# Conductance.net
KiCad netlist of a schematic drawn in EAGLE
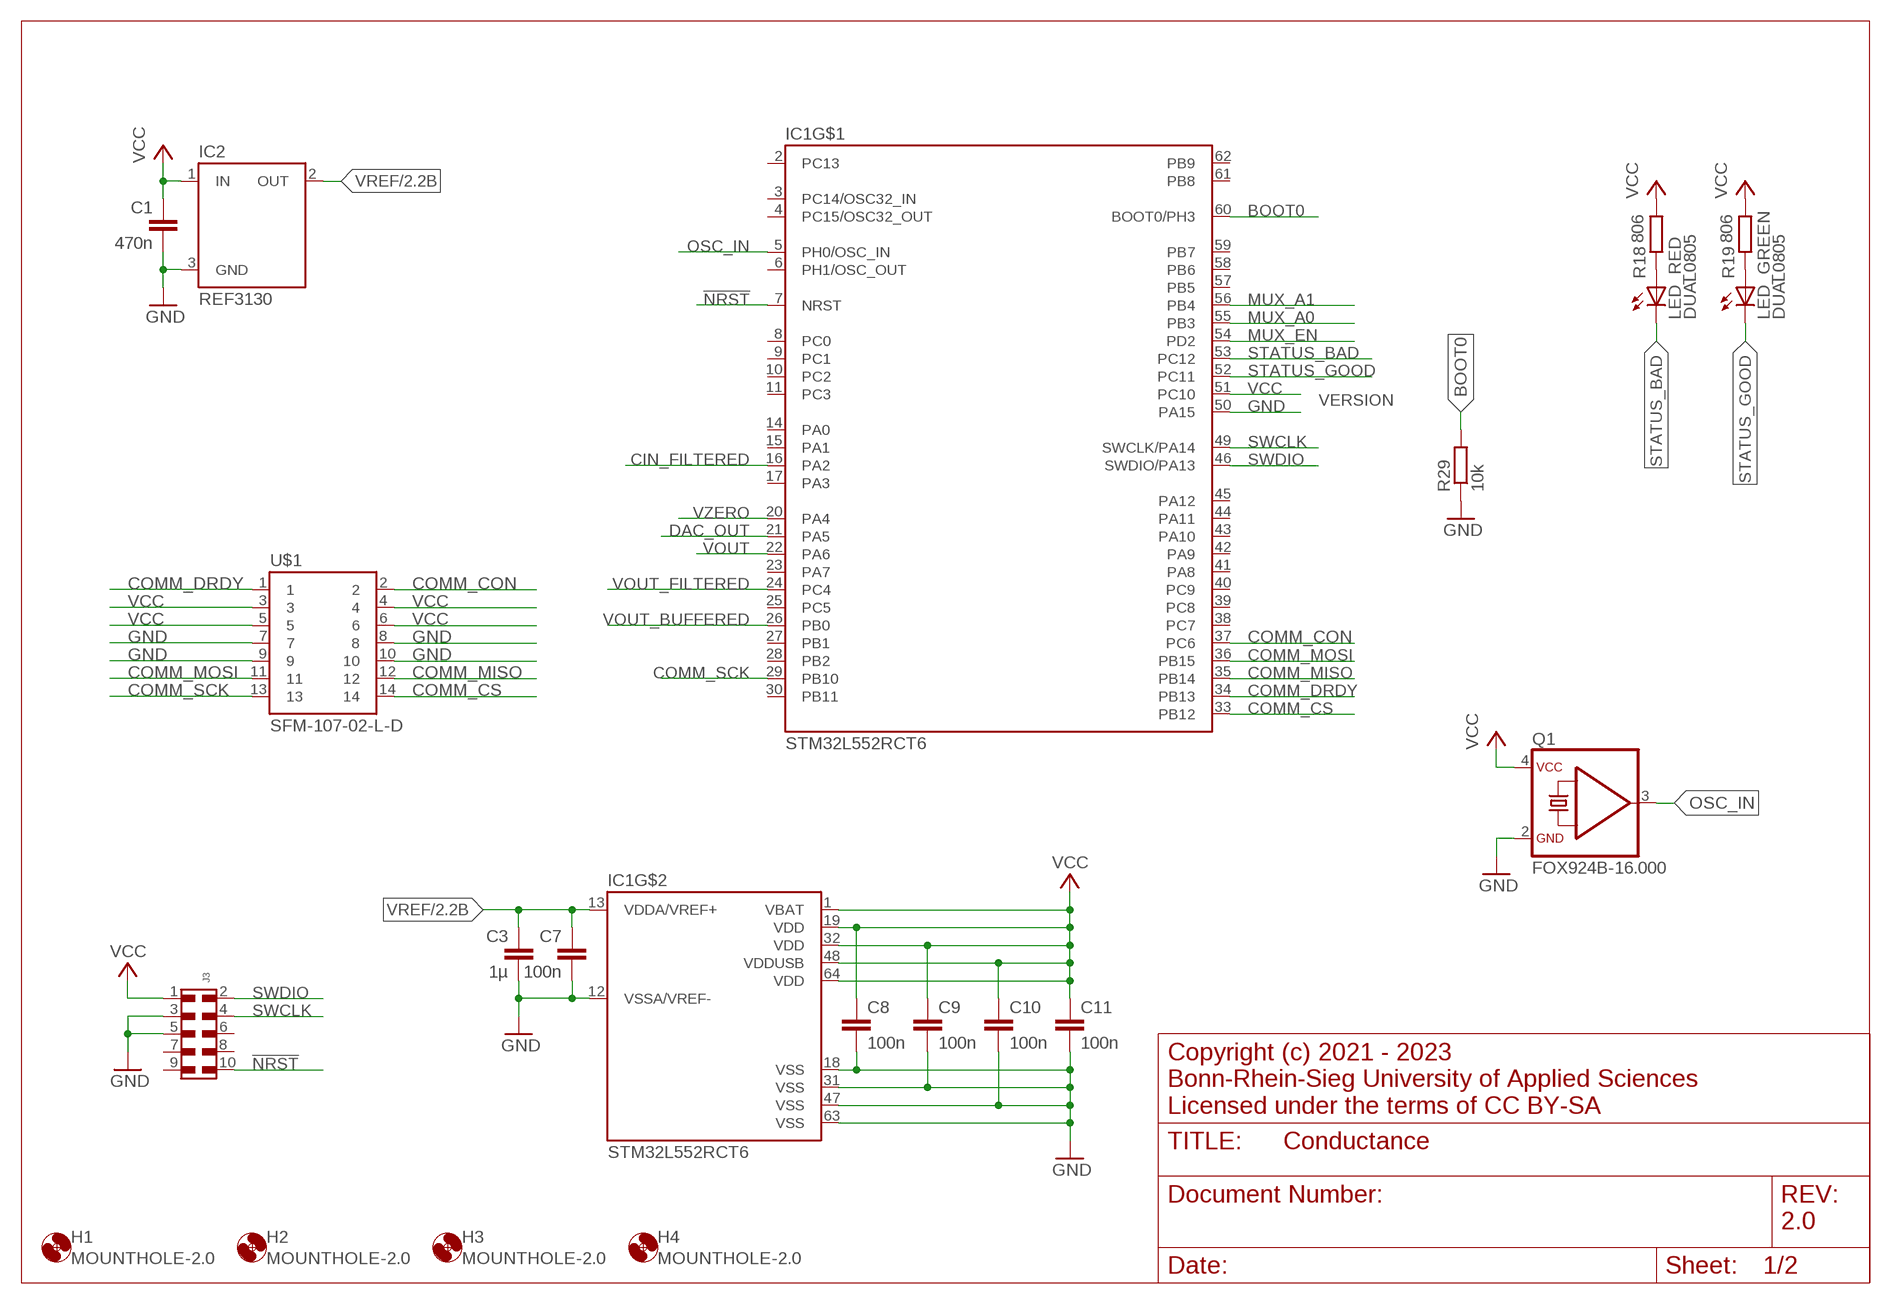
[diagram p0: schematic, sheet 1]
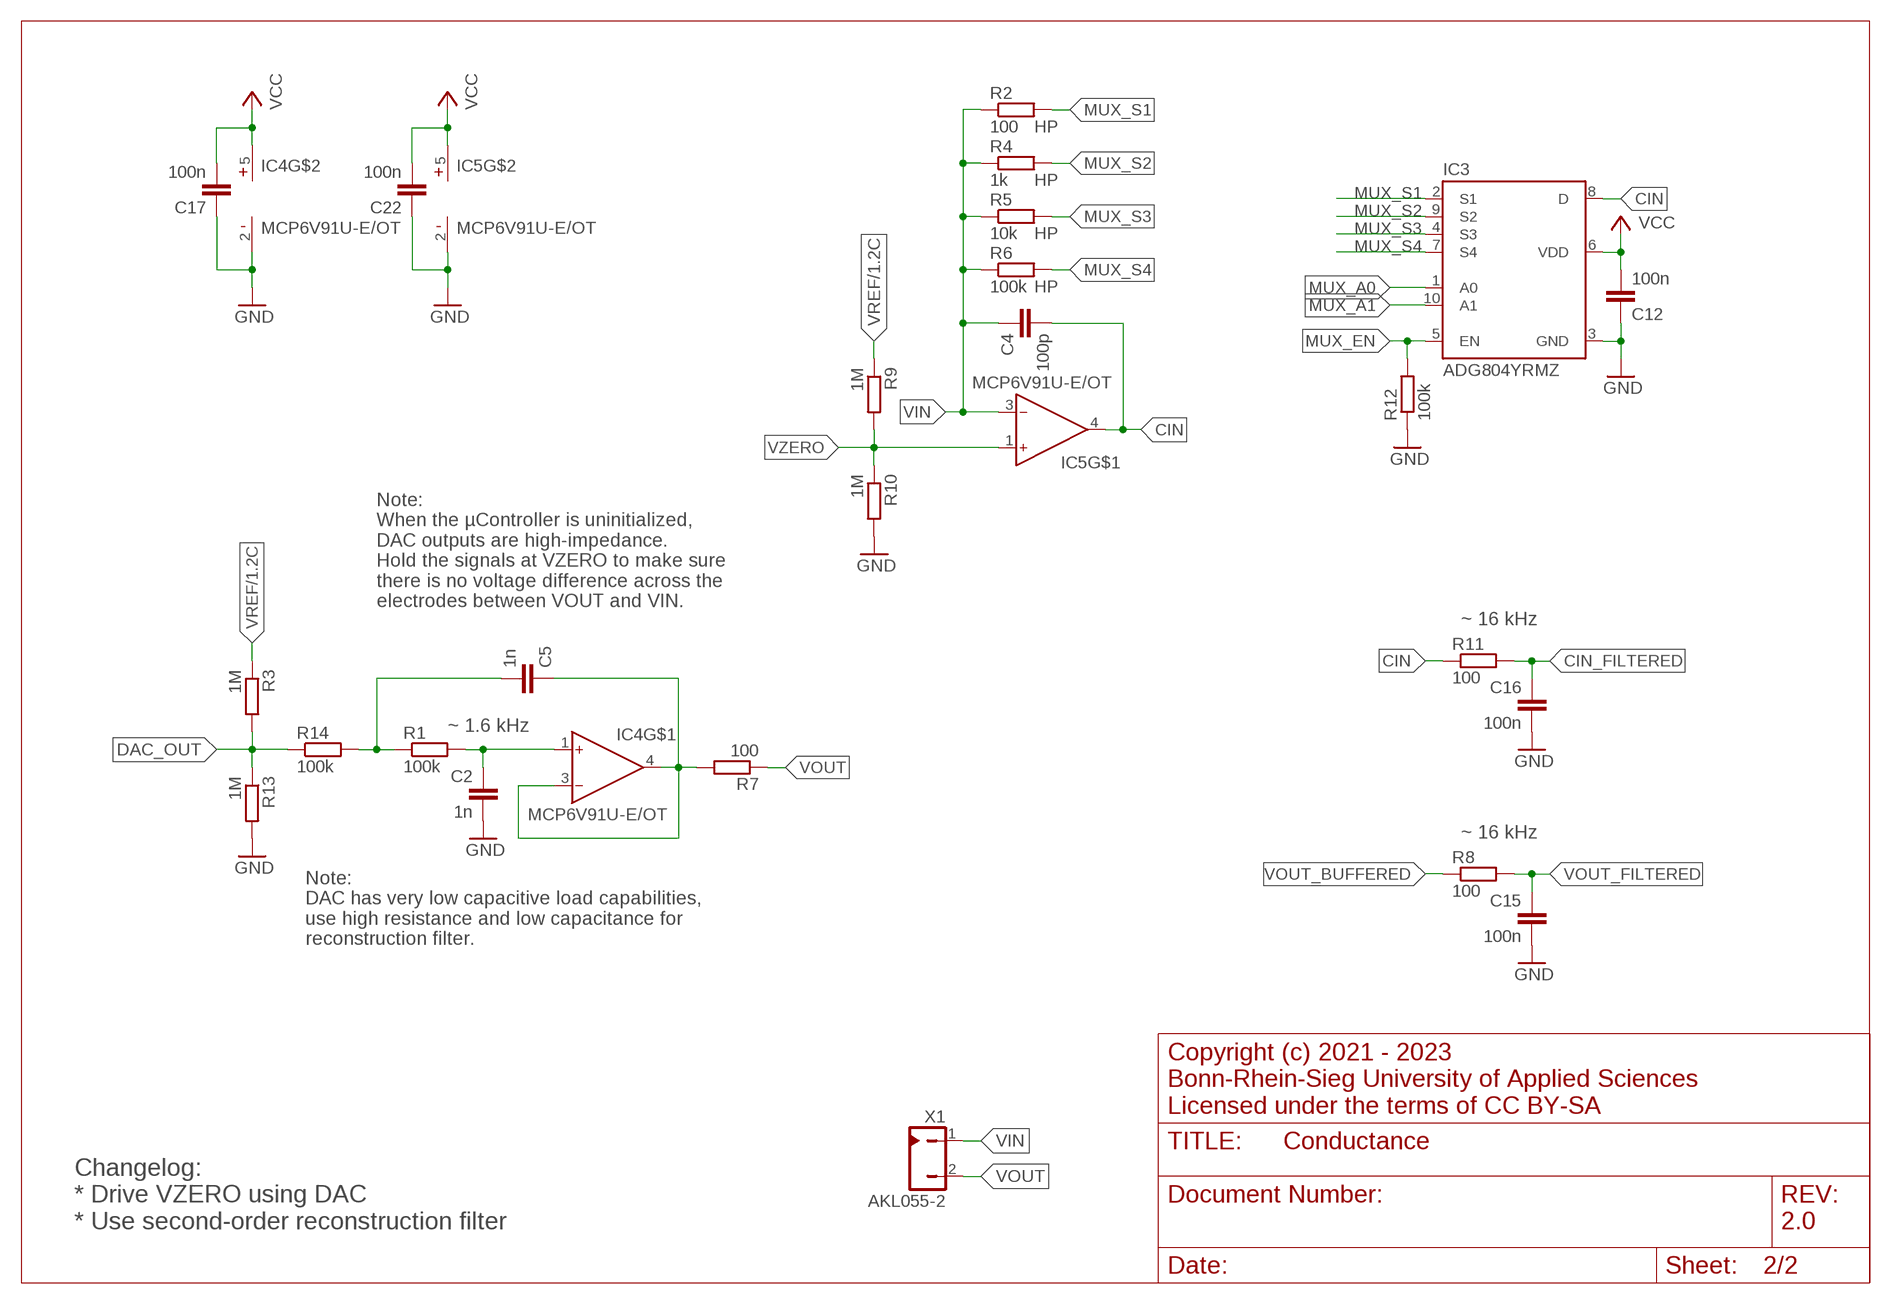
[diagram p1: schematic, sheet 2]

(export (version "E")
  (design (tool "Eeschema 10.0.6"))
  (components
    (comp (ref "C1")
      (value "470n")
      (footprint "eagle-import:C0603")
      (libsource (lib "eagle-import") (part "C-EUC0603"))
    )
    (comp (ref "C3")
      (value "1µ")
      (footprint "eagle-import:C0603")
      (libsource (lib "eagle-import") (part "C-EUC0603"))
    )
    (comp (ref "C7")
      (value "100n")
      (footprint "eagle-import:C0603")
      (libsource (lib "eagle-import") (part "C-EUC0603"))
    )
    (comp (ref "C8")
      (value "100n")
      (footprint "eagle-import:C0603")
      (libsource (lib "eagle-import") (part "C-EUC0603"))
    )
    (comp (ref "C9")
      (value "100n")
      (footprint "eagle-import:C0603")
      (libsource (lib "eagle-import") (part "C-EUC0603"))
    )
    (comp (ref "C10")
      (value "100n")
      (footprint "eagle-import:C0603")
      (libsource (lib "eagle-import") (part "C-EUC0603"))
    )
    (comp (ref "C11")
      (value "100n")
      (footprint "eagle-import:C0603")
      (libsource (lib "eagle-import") (part "C-EUC0603"))
    )
    (comp (ref "H1")
      (value "MOUNTHOLE-2.0")
      (footprint "eagle-import:2.0")
      (libsource (lib "eagle-import") (part "MOUNTHOLE-2.0"))
    )
    (comp (ref "H2")
      (value "MOUNTHOLE-2.0")
      (footprint "eagle-import:2.0")
      (libsource (lib "eagle-import") (part "MOUNTHOLE-2.0"))
    )
    (comp (ref "H3")
      (value "MOUNTHOLE-2.0")
      (footprint "eagle-import:2.0")
      (libsource (lib "eagle-import") (part "MOUNTHOLE-2.0"))
    )
    (comp (ref "H4")
      (value "MOUNTHOLE-2.0")
      (footprint "eagle-import:2.0")
      (libsource (lib "eagle-import") (part "MOUNTHOLE-2.0"))
    )
    (comp (ref "IC1")
      (value "STM32L552RCT6")
      (footprint "eagle-import:LQFP64")
      (libsource (lib "eagle-import") (part "STM32L552R?T6C"))
    )
    (comp (ref "IC2")
      (value "REF3130")
      (footprint "eagle-import:SOT23")
      (libsource (lib "eagle-import") (part "REF3130"))
    )
    (comp (ref "J3")
      (value "6210XX21021_62101021021")
      (footprint "eagle-import:62101021021")
      (libsource (lib "eagle-import") (part "6210XX21021_62101021021"))
    )
    (comp (ref "LED_")
      (value "DUAL0805")
      (footprint "eagle-import:CHIPLEDX2")
      (libsource (lib "eagle-import") (part "DUAL0805"))
    )
    (comp (ref "Q1")
      (value "FOX924B-16.000")
      (footprint "eagle-import:FOX924B")
      (libsource (lib "eagle-import") (part "FOX924B-16.000"))
    )
    (comp (ref "R18")
      (value "806")
      (footprint "eagle-import:R0603")
      (libsource (lib "eagle-import") (part "R-EU_R0603"))
    )
    (comp (ref "R19")
      (value "806")
      (footprint "eagle-import:R0603")
      (libsource (lib "eagle-import") (part "R-EU_R0603"))
    )
    (comp (ref "R29")
      (value "10k")
      (footprint "eagle-import:R0603")
      (libsource (lib "eagle-import") (part "R-EU_R0603"))
    )
    (comp (ref "U$1")
      (value "SFM-107-02-L-D")
      (footprint "eagle-import:SAMTEC-SFM-107-02-L-D")
      (libsource (lib "eagle-import") (part "SFM-107-02-L-D"))
    )
    (comp (ref "C2")
      (value "1n")
      (footprint "eagle-import:C0603")
      (libsource (lib "eagle-import") (part "C-EUC0603"))
    )
    (comp (ref "C4")
      (value "100p")
      (footprint "eagle-import:C0603")
      (libsource (lib "eagle-import") (part "C-EUC0603"))
    )
    (comp (ref "C5")
      (value "1n")
      (footprint "eagle-import:C0603")
      (libsource (lib "eagle-import") (part "C-EUC0603"))
    )
    (comp (ref "C12")
      (value "100n")
      (footprint "eagle-import:C0603")
      (libsource (lib "eagle-import") (part "C-EUC0603"))
    )
    (comp (ref "C15")
      (value "100n")
      (footprint "eagle-import:C0603")
      (libsource (lib "eagle-import") (part "C-EUC0603"))
    )
    (comp (ref "C16")
      (value "100n")
      (footprint "eagle-import:C0603")
      (libsource (lib "eagle-import") (part "C-EUC0603"))
    )
    (comp (ref "C17")
      (value "100n")
      (footprint "eagle-import:C0603")
      (libsource (lib "eagle-import") (part "C-EUC0603"))
    )
    (comp (ref "C22")
      (value "100n")
      (footprint "eagle-import:C0603")
      (libsource (lib "eagle-import") (part "C-EUC0603"))
    )
    (comp (ref "IC3")
      (value "ADG804YRMZ")
      (footprint "eagle-import:MSOP10")
      (libsource (lib "eagle-import") (part "ADG804YRMZ"))
    )
    (comp (ref "IC4")
      (value "MCP6V91U-E/OT")
      (footprint "eagle-import:SOT23-5")
      (libsource (lib "eagle-import") (part "MCP6V91U-/?OTE"))
    )
    (comp (ref "IC5")
      (value "MCP6V91U-E/OT")
      (footprint "eagle-import:SOT23-5")
      (libsource (lib "eagle-import") (part "MCP6V91U-/?OTE"))
    )
    (comp (ref "R1")
      (value "100k")
      (footprint "eagle-import:R0603")
      (libsource (lib "eagle-import") (part "R-EU_R0603"))
    )
    (comp (ref "R2")
      (value "100")
      (footprint "eagle-import:R0603")
      (libsource (lib "eagle-import") (part "R-EU_R0603"))
    )
    (comp (ref "R3")
      (value "1M")
      (footprint "eagle-import:R0603")
      (libsource (lib "eagle-import") (part "R-EU_R0603"))
    )
    (comp (ref "R4")
      (value "1k")
      (footprint "eagle-import:R0603")
      (libsource (lib "eagle-import") (part "R-EU_R0603"))
    )
    (comp (ref "R5")
      (value "10k")
      (footprint "eagle-import:R0603")
      (libsource (lib "eagle-import") (part "R-EU_R0603"))
    )
    (comp (ref "R6")
      (value "100k")
      (footprint "eagle-import:R0603")
      (libsource (lib "eagle-import") (part "R-EU_R0603"))
    )
    (comp (ref "R7")
      (value "100")
      (footprint "eagle-import:R0603")
      (libsource (lib "eagle-import") (part "R-EU_R0603"))
    )
    (comp (ref "R8")
      (value "100")
      (footprint "eagle-import:R0603")
      (libsource (lib "eagle-import") (part "R-EU_R0603"))
    )
    (comp (ref "R9")
      (value "1M")
      (footprint "eagle-import:R0603")
      (libsource (lib "eagle-import") (part "R-EU_R0603"))
    )
    (comp (ref "R10")
      (value "1M")
      (footprint "eagle-import:R0603")
      (libsource (lib "eagle-import") (part "R-EU_R0603"))
    )
    (comp (ref "R11")
      (value "100")
      (footprint "eagle-import:R0603")
      (libsource (lib "eagle-import") (part "R-EU_R0603"))
    )
    (comp (ref "R12")
      (value "100k")
      (footprint "eagle-import:R0603")
      (libsource (lib "eagle-import") (part "R-EU_R0603"))
    )
    (comp (ref "R13")
      (value "1M")
      (footprint "eagle-import:R0603")
      (libsource (lib "eagle-import") (part "R-EU_R0603"))
    )
    (comp (ref "R14")
      (value "100k")
      (footprint "eagle-import:R0603")
      (libsource (lib "eagle-import") (part "R-EU_R0603"))
    )
    (comp (ref "X1")
      (value "AKL055-2")
      (footprint "eagle-import:AKL055-2")
      (libsource (lib "eagle-import") (part "AKL055-2"))
    )
  )
  (nets
    (net (code "1") (name "BOOT0") (class "Default")
      (node (ref "IC1") (pin "60") (pinfunction "BOOT0/PH3_60") (pintype "bidirectional"))
      (node (ref "R29") (pin "2") (pinfunction "2_2") (pintype "passive"))
    )
    (net (code "2") (name "CIN") (class "Default")
      (node (ref "C4") (pin "2") (pinfunction "2_2") (pintype "passive"))
      (node (ref "IC3") (pin "8") (pinfunction "D_8") (pintype "bidirectional"))
      (node (ref "IC5") (pin "4") (pinfunction "OUT_4") (pintype "output"))
      (node (ref "R11") (pin "1") (pinfunction "1_1") (pintype "passive"))
    )
    (net (code "3") (name "CIN_FILTERED") (class "Default")
      (node (ref "C16") (pin "1") (pinfunction "1_1") (pintype "passive"))
      (node (ref "IC1") (pin "16") (pinfunction "PA2_16") (pintype "bidirectional"))
      (node (ref "R11") (pin "2") (pinfunction "2_2") (pintype "passive"))
    )
    (net (code "4") (name "COMM_CON") (class "Default")
      (node (ref "IC1") (pin "37") (pinfunction "PC6_37") (pintype "bidirectional"))
      (node (ref "U$1") (pin "2") (pinfunction "2_2") (pintype "passive"))
    )
    (net (code "5") (name "COMM_CS") (class "Default")
      (node (ref "IC1") (pin "33") (pinfunction "PB12_33") (pintype "bidirectional"))
      (node (ref "U$1") (pin "14") (pinfunction "14_14") (pintype "passive"))
    )
    (net (code "6") (name "COMM_DRDY") (class "Default")
      (node (ref "IC1") (pin "34") (pinfunction "PB13_34") (pintype "bidirectional"))
      (node (ref "U$1") (pin "1") (pinfunction "1_1") (pintype "passive"))
    )
    (net (code "7") (name "COMM_MISO") (class "Default")
      (node (ref "IC1") (pin "35") (pinfunction "PB14_35") (pintype "bidirectional"))
      (node (ref "U$1") (pin "12") (pinfunction "12_12") (pintype "passive"))
    )
    (net (code "8") (name "COMM_MOSI") (class "Default")
      (node (ref "IC1") (pin "36") (pinfunction "PB15_36") (pintype "bidirectional"))
      (node (ref "U$1") (pin "11") (pinfunction "11_11") (pintype "passive"))
    )
    (net (code "9") (name "COMM_SCK") (class "Default")
      (node (ref "IC1") (pin "29") (pinfunction "PB10_29") (pintype "bidirectional"))
      (node (ref "U$1") (pin "13") (pinfunction "13_13") (pintype "passive"))
    )
    (net (code "10") (name "DAC_OUT") (class "Default")
      (node (ref "IC1") (pin "21") (pinfunction "PA5_21") (pintype "bidirectional"))
      (node (ref "R13") (pin "1") (pinfunction "1_1") (pintype "passive"))
      (node (ref "R14") (pin "1") (pinfunction "1_1") (pintype "passive"))
      (node (ref "R3") (pin "2") (pinfunction "2_2") (pintype "passive"))
    )
    (net (code "11") (name "GND") (class "Default")
      (node (ref "C1") (pin "2") (pinfunction "2_2") (pintype "passive"))
      (node (ref "C10") (pin "2") (pinfunction "2_2") (pintype "passive"))
      (node (ref "C11") (pin "2") (pinfunction "2_2") (pintype "passive"))
      (node (ref "C12") (pin "1") (pinfunction "1_1") (pintype "passive"))
      (node (ref "C15") (pin "2") (pinfunction "2_2") (pintype "passive"))
      (node (ref "C16") (pin "2") (pinfunction "2_2") (pintype "passive"))
      (node (ref "C17") (pin "1") (pinfunction "1_1") (pintype "passive"))
      (node (ref "C2") (pin "2") (pinfunction "2_2") (pintype "passive"))
      (node (ref "C22") (pin "1") (pinfunction "1_1") (pintype "passive"))
      (node (ref "C3") (pin "2") (pinfunction "2_2") (pintype "passive"))
      (node (ref "C7") (pin "2") (pinfunction "2_2") (pintype "passive"))
      (node (ref "C8") (pin "2") (pinfunction "2_2") (pintype "passive"))
      (node (ref "C9") (pin "2") (pinfunction "2_2") (pintype "passive"))
      (node (ref "IC1") (pin "12") (pinfunction "VSSA/VREF-_12") (pintype "bidirectional"))
      (node (ref "IC1") (pin "18") (pinfunction "VSS_18") (pintype "bidirectional"))
      (node (ref "IC1") (pin "31") (pinfunction "VSS_31") (pintype "bidirectional"))
      (node (ref "IC1") (pin "47") (pinfunction "VSS_47") (pintype "bidirectional"))
      (node (ref "IC1") (pin "50") (pinfunction "PA15_50") (pintype "bidirectional"))
      (node (ref "IC1") (pin "63") (pinfunction "VSS_63") (pintype "bidirectional"))
      (node (ref "IC2") (pin "3") (pinfunction "GND_3") (pintype "bidirectional"))
      (node (ref "IC3") (pin "3") (pinfunction "GND_3") (pintype "bidirectional"))
      (node (ref "IC4") (pin "2") (pinfunction "VSS_2") (pintype "power_in"))
      (node (ref "IC5") (pin "2") (pinfunction "VSS_2") (pintype "power_in"))
      (node (ref "J3") (pin "3") (pinfunction "3_3") (pintype "passive"))
      (node (ref "J3") (pin "5") (pinfunction "5_5") (pintype "passive"))
      (node (ref "Q1") (pin "2") (pinfunction "GND_2") (pintype "power_in"))
      (node (ref "R10") (pin "2") (pinfunction "2_2") (pintype "passive"))
      (node (ref "R12") (pin "1") (pinfunction "1_1") (pintype "passive"))
      (node (ref "R13") (pin "2") (pinfunction "2_2") (pintype "passive"))
      (node (ref "R29") (pin "1") (pinfunction "1_1") (pintype "passive"))
      (node (ref "U$1") (pin "10") (pinfunction "10_10") (pintype "passive"))
      (node (ref "U$1") (pin "7") (pinfunction "7_7") (pintype "passive"))
      (node (ref "U$1") (pin "8") (pinfunction "8_8") (pintype "passive"))
      (node (ref "U$1") (pin "9") (pinfunction "9_9") (pintype "passive"))
    )
    (net (code "12") (name "MUX_A0") (class "Default")
      (node (ref "IC1") (pin "55") (pinfunction "PB3_55") (pintype "bidirectional"))
      (node (ref "IC3") (pin "1") (pinfunction "A0_1") (pintype "bidirectional"))
    )
    (net (code "13") (name "MUX_A1") (class "Default")
      (node (ref "IC1") (pin "56") (pinfunction "PB4_56") (pintype "bidirectional"))
      (node (ref "IC3") (pin "10") (pinfunction "A1_10") (pintype "bidirectional"))
    )
    (net (code "14") (name "MUX_EN") (class "Default")
      (node (ref "IC1") (pin "54") (pinfunction "PD2_54") (pintype "bidirectional"))
      (node (ref "IC3") (pin "5") (pinfunction "EN_5") (pintype "bidirectional"))
      (node (ref "R12") (pin "2") (pinfunction "2_2") (pintype "passive"))
    )
    (net (code "15") (name "MUX_S1") (class "Default")
      (node (ref "IC3") (pin "2") (pinfunction "S1_2") (pintype "bidirectional"))
      (node (ref "R2") (pin "2") (pinfunction "2_2") (pintype "passive"))
    )
    (net (code "16") (name "MUX_S2") (class "Default")
      (node (ref "IC3") (pin "9") (pinfunction "S2_9") (pintype "bidirectional"))
      (node (ref "R4") (pin "2") (pinfunction "2_2") (pintype "passive"))
    )
    (net (code "17") (name "MUX_S3") (class "Default")
      (node (ref "IC3") (pin "4") (pinfunction "S3_4") (pintype "bidirectional"))
      (node (ref "R5") (pin "2") (pinfunction "2_2") (pintype "passive"))
    )
    (net (code "18") (name "MUX_S4") (class "Default")
      (node (ref "IC3") (pin "7") (pinfunction "S4_7") (pintype "bidirectional"))
      (node (ref "R6") (pin "2") (pinfunction "2_2") (pintype "passive"))
    )
    (net (code "19") (name "Net-(C5-Pad2)") (class "Default")
      (node (ref "C5") (pin "2") (pinfunction "2_2") (pintype "passive"))
      (node (ref "R1") (pin "1") (pinfunction "1_1") (pintype "passive"))
      (node (ref "R14") (pin "2") (pinfunction "2_2") (pintype "passive"))
    )
    (net (code "20") (name "Net-(IC4A-IN+)") (class "Default")
      (node (ref "C2") (pin "1") (pinfunction "1_1") (pintype "passive"))
      (node (ref "IC4") (pin "1") (pinfunction "IN+_1") (pintype "input"))
      (node (ref "R1") (pin "2") (pinfunction "2_2") (pintype "passive"))
    )
    (net (code "21") (name "Net-(IC4A-IN-)") (class "Default")
      (node (ref "C5") (pin "1") (pinfunction "1_1") (pintype "passive"))
      (node (ref "IC4") (pin "3") (pinfunction "IN-_3") (pintype "input"))
      (node (ref "IC4") (pin "4") (pinfunction "OUT_4") (pintype "output"))
      (node (ref "R7") (pin "2") (pinfunction "2_2") (pintype "passive"))
    )
    (net (code "22") (name "Net-(LED_A-A)") (class "Default")
      (node (ref "LED_") (pin "A2") (pinfunction "A_A2") (pintype "passive"))
      (node (ref "R19") (pin "1") (pinfunction "1_1") (pintype "passive"))
    )
    (net (code "23") (name "Net-(LED_B-A)") (class "Default")
      (node (ref "LED_") (pin "A1") (pinfunction "A_A1") (pintype "passive"))
      (node (ref "R18") (pin "1") (pinfunction "1_1") (pintype "passive"))
    )
    (net (code "24") (name "OSC_IN") (class "Default")
      (node (ref "IC1") (pin "5") (pinfunction "PH0/OSC_IN_5") (pintype "bidirectional"))
      (node (ref "Q1") (pin "3") (pinfunction "OUT_3") (pintype "output"))
    )
    (net (code "25") (name "STATUS_BAD") (class "Default")
      (node (ref "IC1") (pin "53") (pinfunction "PC12_53") (pintype "bidirectional"))
      (node (ref "LED_") (pin "C1") (pinfunction "C_C1") (pintype "passive"))
    )
    (net (code "26") (name "STATUS_GOOD") (class "Default")
      (node (ref "IC1") (pin "52") (pinfunction "PC11_52") (pintype "bidirectional"))
      (node (ref "LED_") (pin "C2") (pinfunction "C_C2") (pintype "passive"))
    )
    (net (code "27") (name "SWCLK") (class "Default")
      (node (ref "IC1") (pin "49") (pinfunction "SWCLK/PA14_49") (pintype "bidirectional"))
      (node (ref "J3") (pin "4") (pinfunction "4_4") (pintype "passive"))
    )
    (net (code "28") (name "SWDIO") (class "Default")
      (node (ref "IC1") (pin "46") (pinfunction "SWDIO/PA13_46") (pintype "bidirectional"))
      (node (ref "J3") (pin "2") (pinfunction "2_2") (pintype "passive"))
    )
    (net (code "29") (name "VCC") (class "Default")
      (node (ref "C1") (pin "1") (pinfunction "1_1") (pintype "passive"))
      (node (ref "C10") (pin "1") (pinfunction "1_1") (pintype "passive"))
      (node (ref "C11") (pin "1") (pinfunction "1_1") (pintype "passive"))
      (node (ref "C12") (pin "2") (pinfunction "2_2") (pintype "passive"))
      (node (ref "C17") (pin "2") (pinfunction "2_2") (pintype "passive"))
      (node (ref "C22") (pin "2") (pinfunction "2_2") (pintype "passive"))
      (node (ref "C8") (pin "1") (pinfunction "1_1") (pintype "passive"))
      (node (ref "C9") (pin "1") (pinfunction "1_1") (pintype "passive"))
      (node (ref "IC1") (pin "1") (pinfunction "VBAT_1") (pintype "bidirectional"))
      (node (ref "IC1") (pin "19") (pinfunction "VDD_19") (pintype "bidirectional"))
      (node (ref "IC1") (pin "32") (pinfunction "VDD_32") (pintype "bidirectional"))
      (node (ref "IC1") (pin "48") (pinfunction "VDDUSB_48") (pintype "bidirectional"))
      (node (ref "IC1") (pin "51") (pinfunction "PC10_51") (pintype "bidirectional"))
      (node (ref "IC1") (pin "64") (pinfunction "VDD_64") (pintype "bidirectional"))
      (node (ref "IC2") (pin "1") (pinfunction "IN_1") (pintype "bidirectional"))
      (node (ref "IC3") (pin "6") (pinfunction "VDD_6") (pintype "bidirectional"))
      (node (ref "IC4") (pin "5") (pinfunction "VDD_5") (pintype "power_in"))
      (node (ref "IC5") (pin "5") (pinfunction "VDD_5") (pintype "power_in"))
      (node (ref "J3") (pin "1") (pinfunction "1_1") (pintype "passive"))
      (node (ref "Q1") (pin "4") (pinfunction "VCC_4") (pintype "power_in"))
      (node (ref "R18") (pin "2") (pinfunction "2_2") (pintype "passive"))
      (node (ref "R19") (pin "2") (pinfunction "2_2") (pintype "passive"))
      (node (ref "U$1") (pin "3") (pinfunction "3_3") (pintype "passive"))
      (node (ref "U$1") (pin "4") (pinfunction "4_4") (pintype "passive"))
      (node (ref "U$1") (pin "5") (pinfunction "5_5") (pintype "passive"))
      (node (ref "U$1") (pin "6") (pinfunction "6_6") (pintype "passive"))
    )
    (net (code "30") (name "VIN") (class "Default")
      (node (ref "C4") (pin "1") (pinfunction "1_1") (pintype "passive"))
      (node (ref "IC5") (pin "3") (pinfunction "IN-_3") (pintype "input"))
      (node (ref "R2") (pin "1") (pinfunction "1_1") (pintype "passive"))
      (node (ref "R4") (pin "1") (pinfunction "1_1") (pintype "passive"))
      (node (ref "R5") (pin "1") (pinfunction "1_1") (pintype "passive"))
      (node (ref "R6") (pin "1") (pinfunction "1_1") (pintype "passive"))
      (node (ref "X1") (pin "1") (pinfunction "1_1") (pintype "passive"))
    )
    (net (code "31") (name "VOUT") (class "Default")
      (node (ref "IC1") (pin "22") (pinfunction "PA6_22") (pintype "bidirectional"))
      (node (ref "R7") (pin "1") (pinfunction "1_1") (pintype "passive"))
      (node (ref "X1") (pin "2") (pinfunction "4_2") (pintype "passive"))
    )
    (net (code "32") (name "VOUT_BUFFERED") (class "Default")
      (node (ref "IC1") (pin "26") (pinfunction "PB0_26") (pintype "bidirectional"))
      (node (ref "R8") (pin "1") (pinfunction "1_1") (pintype "passive"))
    )
    (net (code "33") (name "VOUT_FILTERED") (class "Default")
      (node (ref "C15") (pin "1") (pinfunction "1_1") (pintype "passive"))
      (node (ref "IC1") (pin "24") (pinfunction "PC4_24") (pintype "bidirectional"))
      (node (ref "R8") (pin "2") (pinfunction "2_2") (pintype "passive"))
    )
    (net (code "34") (name "VREF") (class "Default")
      (node (ref "C3") (pin "1") (pinfunction "1_1") (pintype "passive"))
      (node (ref "C7") (pin "1") (pinfunction "1_1") (pintype "passive"))
      (node (ref "IC1") (pin "13") (pinfunction "VDDA/VREF+_13") (pintype "bidirectional"))
      (node (ref "IC2") (pin "2") (pinfunction "OUT_2") (pintype "bidirectional"))
      (node (ref "R3") (pin "1") (pinfunction "1_1") (pintype "passive"))
      (node (ref "R9") (pin "1") (pinfunction "1_1") (pintype "passive"))
    )
    (net (code "35") (name "VZERO") (class "Default")
      (node (ref "IC1") (pin "20") (pinfunction "PA4_20") (pintype "bidirectional"))
      (node (ref "IC5") (pin "1") (pinfunction "IN+_1") (pintype "input"))
      (node (ref "R10") (pin "1") (pinfunction "1_1") (pintype "passive"))
      (node (ref "R9") (pin "2") (pinfunction "2_2") (pintype "passive"))
    )
    (net (code "36") (name "unconnected-(IC1A-PA0-Pad14)") (class "Default")
      (node (ref "IC1") (pin "14") (pinfunction "PA0_14") (pintype "bidirectional"))
    )
    (net (code "37") (name "unconnected-(IC1A-PA1-Pad15)") (class "Default")
      (node (ref "IC1") (pin "15") (pinfunction "PA1_15") (pintype "bidirectional"))
    )
    (net (code "38") (name "unconnected-(IC1A-PA3-Pad17)") (class "Default")
      (node (ref "IC1") (pin "17") (pinfunction "PA3_17") (pintype "bidirectional"))
    )
    (net (code "39") (name "unconnected-(IC1A-PA7-Pad23)") (class "Default")
      (node (ref "IC1") (pin "23") (pinfunction "PA7_23") (pintype "bidirectional"))
    )
    (net (code "40") (name "unconnected-(IC1A-PA8-Pad41)") (class "Default")
      (node (ref "IC1") (pin "41") (pinfunction "PA8_41") (pintype "bidirectional"))
    )
    (net (code "41") (name "unconnected-(IC1A-PA9-Pad42)") (class "Default")
      (node (ref "IC1") (pin "42") (pinfunction "PA9_42") (pintype "bidirectional"))
    )
    (net (code "42") (name "unconnected-(IC1A-PA10-Pad43)") (class "Default")
      (node (ref "IC1") (pin "43") (pinfunction "PA10_43") (pintype "bidirectional"))
    )
    (net (code "43") (name "unconnected-(IC1A-PA11-Pad44)") (class "Default")
      (node (ref "IC1") (pin "44") (pinfunction "PA11_44") (pintype "bidirectional"))
    )
    (net (code "44") (name "unconnected-(IC1A-PA12-Pad45)") (class "Default")
      (node (ref "IC1") (pin "45") (pinfunction "PA12_45") (pintype "bidirectional"))
    )
    (net (code "45") (name "unconnected-(IC1A-PB1-Pad27)") (class "Default")
      (node (ref "IC1") (pin "27") (pinfunction "PB1_27") (pintype "bidirectional"))
    )
    (net (code "46") (name "unconnected-(IC1A-PB2-Pad28)") (class "Default")
      (node (ref "IC1") (pin "28") (pinfunction "PB2_28") (pintype "bidirectional"))
    )
    (net (code "47") (name "unconnected-(IC1A-PB5-Pad57)") (class "Default")
      (node (ref "IC1") (pin "57") (pinfunction "PB5_57") (pintype "bidirectional"))
    )
    (net (code "48") (name "unconnected-(IC1A-PB6-Pad58)") (class "Default")
      (node (ref "IC1") (pin "58") (pinfunction "PB6_58") (pintype "bidirectional"))
    )
    (net (code "49") (name "unconnected-(IC1A-PB7-Pad59)") (class "Default")
      (node (ref "IC1") (pin "59") (pinfunction "PB7_59") (pintype "bidirectional"))
    )
    (net (code "50") (name "unconnected-(IC1A-PB8-Pad61)") (class "Default")
      (node (ref "IC1") (pin "61") (pinfunction "PB8_61") (pintype "bidirectional"))
    )
    (net (code "51") (name "unconnected-(IC1A-PB9-Pad62)") (class "Default")
      (node (ref "IC1") (pin "62") (pinfunction "PB9_62") (pintype "bidirectional"))
    )
    (net (code "52") (name "unconnected-(IC1A-PB11-Pad30)") (class "Default")
      (node (ref "IC1") (pin "30") (pinfunction "PB11_30") (pintype "bidirectional"))
    )
    (net (code "53") (name "unconnected-(IC1A-PC0-Pad8)") (class "Default")
      (node (ref "IC1") (pin "8") (pinfunction "PC0_8") (pintype "bidirectional"))
    )
    (net (code "54") (name "unconnected-(IC1A-PC1-Pad9)") (class "Default")
      (node (ref "IC1") (pin "9") (pinfunction "PC1_9") (pintype "bidirectional"))
    )
    (net (code "55") (name "unconnected-(IC1A-PC2-Pad10)") (class "Default")
      (node (ref "IC1") (pin "10") (pinfunction "PC2_10") (pintype "bidirectional"))
    )
    (net (code "56") (name "unconnected-(IC1A-PC3-Pad11)") (class "Default")
      (node (ref "IC1") (pin "11") (pinfunction "PC3_11") (pintype "bidirectional"))
    )
    (net (code "57") (name "unconnected-(IC1A-PC5-Pad25)") (class "Default")
      (node (ref "IC1") (pin "25") (pinfunction "PC5_25") (pintype "bidirectional"))
    )
    (net (code "58") (name "unconnected-(IC1A-PC7-Pad38)") (class "Default")
      (node (ref "IC1") (pin "38") (pinfunction "PC7_38") (pintype "bidirectional"))
    )
    (net (code "59") (name "unconnected-(IC1A-PC8-Pad39)") (class "Default")
      (node (ref "IC1") (pin "39") (pinfunction "PC8_39") (pintype "bidirectional"))
    )
    (net (code "60") (name "unconnected-(IC1A-PC9-Pad40)") (class "Default")
      (node (ref "IC1") (pin "40") (pinfunction "PC9_40") (pintype "bidirectional"))
    )
    (net (code "61") (name "unconnected-(IC1A-PC13-Pad2)") (class "Default")
      (node (ref "IC1") (pin "2") (pinfunction "PC13_2") (pintype "bidirectional"))
    )
    (net (code "62") (name "unconnected-(IC1A-PC14{slash}OSC32_IN-Pad3)") (class "Default")
      (node (ref "IC1") (pin "3") (pinfunction "PC14/OSC32_IN_3") (pintype "bidirectional"))
    )
    (net (code "63") (name "unconnected-(IC1A-PC15{slash}OSC32_OUT-Pad4)") (class "Default")
      (node (ref "IC1") (pin "4") (pinfunction "PC15/OSC32_OUT_4") (pintype "bidirectional"))
    )
    (net (code "64") (name "unconnected-(IC1A-PH1{slash}OSC_OUT-Pad6)") (class "Default")
      (node (ref "IC1") (pin "6") (pinfunction "PH1/OSC_OUT_6") (pintype "bidirectional"))
    )
    (net (code "65") (name "unconnected-(J3-Pad6)") (class "Default")
      (node (ref "J3") (pin "6") (pinfunction "6_6") (pintype "passive"))
    )
    (net (code "66") (name "unconnected-(J3-Pad7)") (class "Default")
      (node (ref "J3") (pin "7") (pinfunction "7_7") (pintype "passive"))
    )
    (net (code "67") (name "unconnected-(J3-Pad8)") (class "Default")
      (node (ref "J3") (pin "8") (pinfunction "8_8") (pintype "passive"))
    )
    (net (code "68") (name "unconnected-(J3-Pad9)") (class "Default")
      (node (ref "J3") (pin "9") (pinfunction "9_9") (pintype "passive"))
    )
    (net (code "69") (name "~{NRST}") (class "Default")
      (node (ref "IC1") (pin "7") (pinfunction "NRST_7") (pintype "bidirectional"))
      (node (ref "J3") (pin "10") (pinfunction "10_10") (pintype "passive"))
    )
  )
)
